# Shield.net
KiCad netlist of a schematic drawn in EAGLE
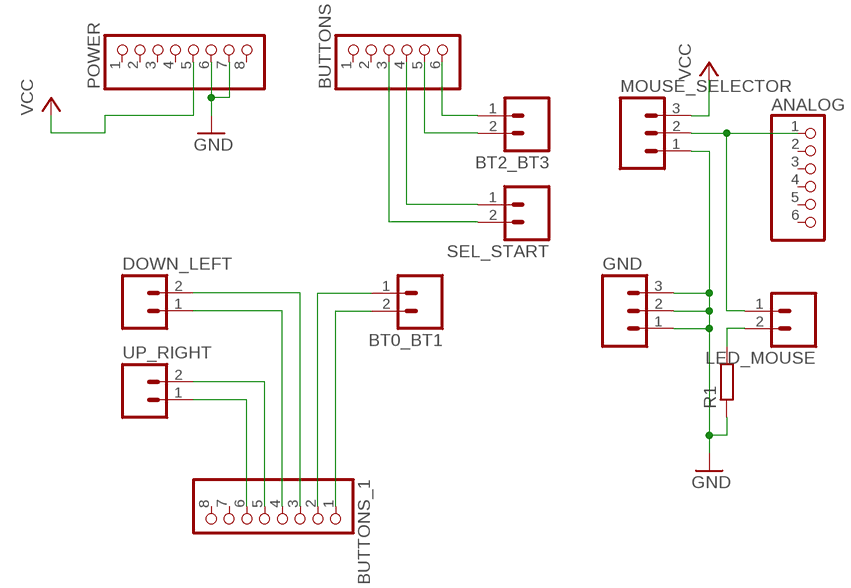
[diagram p0: schematic, sheet 1]

(export (version "E")
  (design (tool "Eeschema 10.0.6"))
  (components
    (comp (ref "ANALOG")
      (value "PINHD-1X6")
      (footprint "eagle-import:1X06")
      (libsource (lib "eagle-import") (part "PINHD-1X6"))
    )
    (comp (ref "BT0_BT1")
      (value "M023.5MM")
      (footprint "eagle-import:SCREWTERMINAL-3.5MM-2")
      (libsource (lib "eagle-import") (part "M023.5MM"))
    )
    (comp (ref "BT2_BT3")
      (value "M023.5MM")
      (footprint "eagle-import:SCREWTERMINAL-3.5MM-2")
      (libsource (lib "eagle-import") (part "M023.5MM"))
    )
    (comp (ref "BUTTONS")
      (value "PINHD-1X6")
      (footprint "eagle-import:1X06")
      (libsource (lib "eagle-import") (part "PINHD-1X6"))
    )
    (comp (ref "BUTTONS_1")
      (value "PINHD-1X8BIG")
      (footprint "eagle-import:1X08-BIG")
      (libsource (lib "eagle-import") (part "PINHD-1X8BIG"))
    )
    (comp (ref "DOWN_LEFT")
      (value "M023.5MM")
      (footprint "eagle-import:SCREWTERMINAL-3.5MM-2")
      (libsource (lib "eagle-import") (part "M023.5MM"))
    )
    (comp (ref "GND")
      (value "M03SCREW")
      (footprint "eagle-import:SCREWTERMINAL-3.5MM-3")
      (libsource (lib "eagle-import") (part "M03SCREW"))
    )
    (comp (ref "LED_MOUSE")
      (value "M023.5MM")
      (footprint "eagle-import:SCREWTERMINAL-3.5MM-2")
      (libsource (lib "eagle-import") (part "M023.5MM"))
    )
    (comp (ref "MOUSE_SELECTOR")
      (value "M03SCREW")
      (footprint "eagle-import:SCREWTERMINAL-3.5MM-3")
      (libsource (lib "eagle-import") (part "M03SCREW"))
    )
    (comp (ref "POWER")
      (value "PINHD-1X8BIG")
      (footprint "eagle-import:1X08-BIG")
      (libsource (lib "eagle-import") (part "PINHD-1X8BIG"))
    )
    (comp (ref "R1")
      (value "R-EU_0204/7")
      (footprint "eagle-import:0204_7")
      (libsource (lib "eagle-import") (part "R-EU_0204/7"))
    )
    (comp (ref "SEL_START")
      (value "M023.5MM")
      (footprint "eagle-import:SCREWTERMINAL-3.5MM-2")
      (libsource (lib "eagle-import") (part "M023.5MM"))
    )
    (comp (ref "UP_RIGHT")
      (value "M023.5MM")
      (footprint "eagle-import:SCREWTERMINAL-3.5MM-2")
      (libsource (lib "eagle-import") (part "M023.5MM"))
    )
  )
  (nets
    (net (code "1") (name "GND") (class "Default")
      (node (ref "GND") (pin "1") (pinfunction "1_1") (pintype "passive"))
      (node (ref "GND") (pin "2") (pinfunction "2_2") (pintype "passive"))
      (node (ref "GND") (pin "3") (pinfunction "3_3") (pintype "passive"))
      (node (ref "MOUSE_SELECTOR") (pin "1") (pinfunction "1_1") (pintype "passive"))
      (node (ref "POWER") (pin "6") (pinfunction "6_6") (pintype "passive"))
      (node (ref "POWER") (pin "7") (pinfunction "7_7") (pintype "passive"))
      (node (ref "R1") (pin "1") (pinfunction "1_1") (pintype "passive"))
    )
    (net (code "2") (name "Net-(ANALOG-Pad1)") (class "Default")
      (node (ref "ANALOG") (pin "1") (pinfunction "1_1") (pintype "passive"))
      (node (ref "LED_MOUSE") (pin "1") (pinfunction "1_1") (pintype "passive"))
      (node (ref "MOUSE_SELECTOR") (pin "2") (pinfunction "2_2") (pintype "passive"))
    )
    (net (code "3") (name "Net-(BT0_BT1-Pad1)") (class "Default")
      (node (ref "BT0_BT1") (pin "1") (pinfunction "1_1") (pintype "passive"))
      (node (ref "BUTTONS_1") (pin "2") (pinfunction "2_2") (pintype "passive"))
    )
    (net (code "4") (name "Net-(BT0_BT1-Pad2)") (class "Default")
      (node (ref "BT0_BT1") (pin "2") (pinfunction "2_2") (pintype "passive"))
      (node (ref "BUTTONS_1") (pin "1") (pinfunction "1_1") (pintype "passive"))
    )
    (net (code "5") (name "Net-(BT2_BT3-Pad1)") (class "Default")
      (node (ref "BT2_BT3") (pin "1") (pinfunction "1_1") (pintype "passive"))
      (node (ref "BUTTONS") (pin "6") (pinfunction "6_6") (pintype "passive"))
    )
    (net (code "6") (name "Net-(BT2_BT3-Pad2)") (class "Default")
      (node (ref "BT2_BT3") (pin "2") (pinfunction "2_2") (pintype "passive"))
      (node (ref "BUTTONS") (pin "5") (pinfunction "5_5") (pintype "passive"))
    )
    (net (code "7") (name "Net-(BUTTONS-Pad3)") (class "Default")
      (node (ref "BUTTONS") (pin "3") (pinfunction "3_3") (pintype "passive"))
      (node (ref "SEL_START") (pin "2") (pinfunction "2_2") (pintype "passive"))
    )
    (net (code "8") (name "Net-(BUTTONS-Pad4)") (class "Default")
      (node (ref "BUTTONS") (pin "4") (pinfunction "4_4") (pintype "passive"))
      (node (ref "SEL_START") (pin "1") (pinfunction "1_1") (pintype "passive"))
    )
    (net (code "9") (name "Net-(BUTTONS_1-Pad3)") (class "Default")
      (node (ref "BUTTONS_1") (pin "3") (pinfunction "3_3") (pintype "passive"))
      (node (ref "DOWN_LEFT") (pin "2") (pinfunction "2_2") (pintype "passive"))
    )
    (net (code "10") (name "Net-(BUTTONS_1-Pad4)") (class "Default")
      (node (ref "BUTTONS_1") (pin "4") (pinfunction "4_4") (pintype "passive"))
      (node (ref "DOWN_LEFT") (pin "1") (pinfunction "1_1") (pintype "passive"))
    )
    (net (code "11") (name "Net-(BUTTONS_1-Pad5)") (class "Default")
      (node (ref "BUTTONS_1") (pin "5") (pinfunction "5_5") (pintype "passive"))
      (node (ref "UP_RIGHT") (pin "2") (pinfunction "2_2") (pintype "passive"))
    )
    (net (code "12") (name "Net-(BUTTONS_1-Pad6)") (class "Default")
      (node (ref "BUTTONS_1") (pin "6") (pinfunction "6_6") (pintype "passive"))
      (node (ref "UP_RIGHT") (pin "1") (pinfunction "1_1") (pintype "passive"))
    )
    (net (code "13") (name "Net-(LED_MOUSE-Pad2)") (class "Default")
      (node (ref "LED_MOUSE") (pin "2") (pinfunction "2_2") (pintype "passive"))
      (node (ref "R1") (pin "2") (pinfunction "2_2") (pintype "passive"))
    )
    (net (code "14") (name "VCC") (class "Default")
      (node (ref "MOUSE_SELECTOR") (pin "3") (pinfunction "3_3") (pintype "passive"))
      (node (ref "POWER") (pin "5") (pinfunction "5_5") (pintype "passive"))
    )
    (net (code "15") (name "unconnected-(ANALOG-Pad2)") (class "Default")
      (node (ref "ANALOG") (pin "2") (pinfunction "2_2") (pintype "passive"))
    )
    (net (code "16") (name "unconnected-(ANALOG-Pad3)") (class "Default")
      (node (ref "ANALOG") (pin "3") (pinfunction "3_3") (pintype "passive"))
    )
    (net (code "17") (name "unconnected-(ANALOG-Pad4)") (class "Default")
      (node (ref "ANALOG") (pin "4") (pinfunction "4_4") (pintype "passive"))
    )
    (net (code "18") (name "unconnected-(ANALOG-Pad5)") (class "Default")
      (node (ref "ANALOG") (pin "5") (pinfunction "5_5") (pintype "passive"))
    )
    (net (code "19") (name "unconnected-(ANALOG-Pad6)") (class "Default")
      (node (ref "ANALOG") (pin "6") (pinfunction "6_6") (pintype "passive"))
    )
    (net (code "20") (name "unconnected-(BUTTONS-Pad1)") (class "Default")
      (node (ref "BUTTONS") (pin "1") (pinfunction "1_1") (pintype "passive"))
    )
    (net (code "21") (name "unconnected-(BUTTONS-Pad2)") (class "Default")
      (node (ref "BUTTONS") (pin "2") (pinfunction "2_2") (pintype "passive"))
    )
    (net (code "22") (name "unconnected-(BUTTONS_1-Pad7)") (class "Default")
      (node (ref "BUTTONS_1") (pin "7") (pinfunction "7_7") (pintype "passive"))
    )
    (net (code "23") (name "unconnected-(BUTTONS_1-Pad8)") (class "Default")
      (node (ref "BUTTONS_1") (pin "8") (pinfunction "8_8") (pintype "passive"))
    )
    (net (code "24") (name "unconnected-(POWER-Pad1)") (class "Default")
      (node (ref "POWER") (pin "1") (pinfunction "1_1") (pintype "passive"))
    )
    (net (code "25") (name "unconnected-(POWER-Pad2)") (class "Default")
      (node (ref "POWER") (pin "2") (pinfunction "2_2") (pintype "passive"))
    )
    (net (code "26") (name "unconnected-(POWER-Pad3)") (class "Default")
      (node (ref "POWER") (pin "3") (pinfunction "3_3") (pintype "passive"))
    )
    (net (code "27") (name "unconnected-(POWER-Pad4)") (class "Default")
      (node (ref "POWER") (pin "4") (pinfunction "4_4") (pintype "passive"))
    )
    (net (code "28") (name "unconnected-(POWER-Pad8)") (class "Default")
      (node (ref "POWER") (pin "8") (pinfunction "8_8") (pintype "passive"))
    )
  )
)
